# caphumidsens2_rev1_rc1.net
KiCad netlist of a schematic drawn in EAGLE
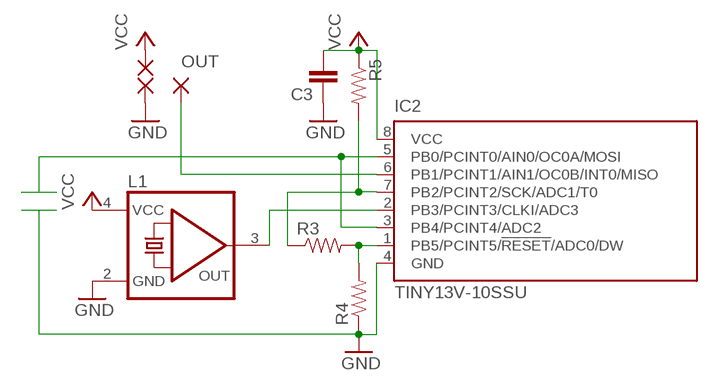
[diagram p0: schematic, sheet 1]

(export (version "E")
  (design (tool "Eeschema 10.0.6"))
  (components
    (comp (ref "C3")
      (value "CAP0805")
      (footprint "eagle-import:0805")
      (libsource (lib "eagle-import") (part "CAP0805"))
    )
    (comp (ref "GND")
      (value "WIREPADSMD2,54-5,08")
      (footprint "eagle-import:SMD1,27-2,54")
      (libsource (lib "eagle-import") (part "SMD2"))
    )
    (comp (ref "IC2")
      (value "TINY13V-10SSU")
      (footprint "eagle-import:8S1")
      (fields (field (name "MPN") "ATTINY13V-10SSU"))
      (libsource (lib "eagle-import") (part "TINY13SSUV-10"))
    )
    (comp (ref "L1")
      (value "XO32-OSCILLATOR")
      (footprint "eagle-import:XO32")
      (libsource (lib "eagle-import") (part "XO32-OSCILLATOR"))
    )
    (comp (ref "OUT")
      (value "WIREPADSMD2,54-5,08")
      (footprint "eagle-import:SMD1,27-2,54")
      (libsource (lib "eagle-import") (part "SMD2"))
    )
    (comp (ref "R3")
      (value "RESISTOR0805-RES")
      (footprint "eagle-import:0805")
      (libsource (lib "eagle-import") (part "RESISTOR0805-RES"))
    )
    (comp (ref "R4")
      (value "RESISTOR0805-RES")
      (footprint "eagle-import:0805")
      (libsource (lib "eagle-import") (part "RESISTOR0805-RES"))
    )
    (comp (ref "R5")
      (value "RESISTOR0805-RES")
      (footprint "eagle-import:0805")
      (libsource (lib "eagle-import") (part "RESISTOR0805-RES"))
    )
    (comp (ref "VCC")
      (value "WIREPADSMD2,54-5,08")
      (footprint "eagle-import:SMD1,27-2,54")
      (libsource (lib "eagle-import") (part "SMD2"))
    )
  )
  (nets
    (net (code "1") (name "/OUT") (class "Default")
      (node (ref "IC2") (pin "6") (pinfunction "PB1/PCINT1/AIN1/OC0B/INT0/MISO_6") (pintype "bidirectional"))
      (node (ref "OUT") (pin "1") (pinfunction "P_1") (pintype "passive"))
    )
    (net (code "2") (name "GND") (class "Default")
      (node (ref "C3") (pin "1") (pinfunction "1_1") (pintype "passive"))
      (node (ref "GND") (pin "1") (pinfunction "P_1") (pintype "passive"))
      (node (ref "IC2") (pin "4") (pinfunction "GND_4") (pintype "power_in"))
      (node (ref "L1") (pin "2") (pinfunction "GND_2") (pintype "power_in"))
      (node (ref "R4") (pin "1") (pinfunction "1_1") (pintype "passive"))
    )
    (net (code "3") (name "Net-(IC2-PB0{slash}PCINT0{slash}AIN0{slash}OC0A{slash}MOSI)") (class "Default")
      (node (ref "IC2") (pin "3") (pinfunction "PB4/PCINT4/ADC2_3") (pintype "bidirectional"))
      (node (ref "IC2") (pin "5") (pinfunction "PB0/PCINT0/AIN0/OC0A/MOSI_5") (pintype "bidirectional"))
    )
    (net (code "4") (name "Net-(IC2-PB2{slash}PCINT2{slash}SCK{slash}ADC1{slash}T0)") (class "Default")
      (node (ref "IC2") (pin "7") (pinfunction "PB2/PCINT2/SCK/ADC1/T0_7") (pintype "bidirectional"))
      (node (ref "R3") (pin "1") (pinfunction "1_1") (pintype "passive"))
      (node (ref "R5") (pin "2") (pinfunction "2_2") (pintype "passive"))
    )
    (net (code "5") (name "Net-(IC2-PB3{slash}PCINT3{slash}CLKI{slash}ADC3)") (class "Default")
      (node (ref "IC2") (pin "2") (pinfunction "PB3/PCINT3/CLKI/ADC3_2") (pintype "bidirectional"))
      (node (ref "L1") (pin "3") (pinfunction "OUT_3") (pintype "output"))
    )
    (net (code "6") (name "Net-(IC2-PB5{slash}PCINT5{slash}~{RESET}{slash}ADC0{slash}DW)") (class "Default")
      (node (ref "IC2") (pin "1") (pinfunction "PB5/PCINT5/~{RESET}/ADC0/DW_1") (pintype "bidirectional"))
      (node (ref "R3") (pin "2") (pinfunction "2_2") (pintype "passive"))
      (node (ref "R4") (pin "2") (pinfunction "2_2") (pintype "passive"))
    )
    (net (code "7") (name "VCC") (class "Default")
      (node (ref "C3") (pin "2") (pinfunction "2_2") (pintype "passive"))
      (node (ref "IC2") (pin "8") (pinfunction "VCC_8") (pintype "power_in"))
      (node (ref "L1") (pin "4") (pinfunction "VCC_4") (pintype "power_in"))
      (node (ref "R5") (pin "1") (pinfunction "1_1") (pintype "passive"))
      (node (ref "VCC") (pin "1") (pinfunction "P_1") (pintype "passive"))
    )
  )
)
